# 4digitSSD-MAX7219CNG.net
KiCad netlist of a schematic drawn in EAGLE
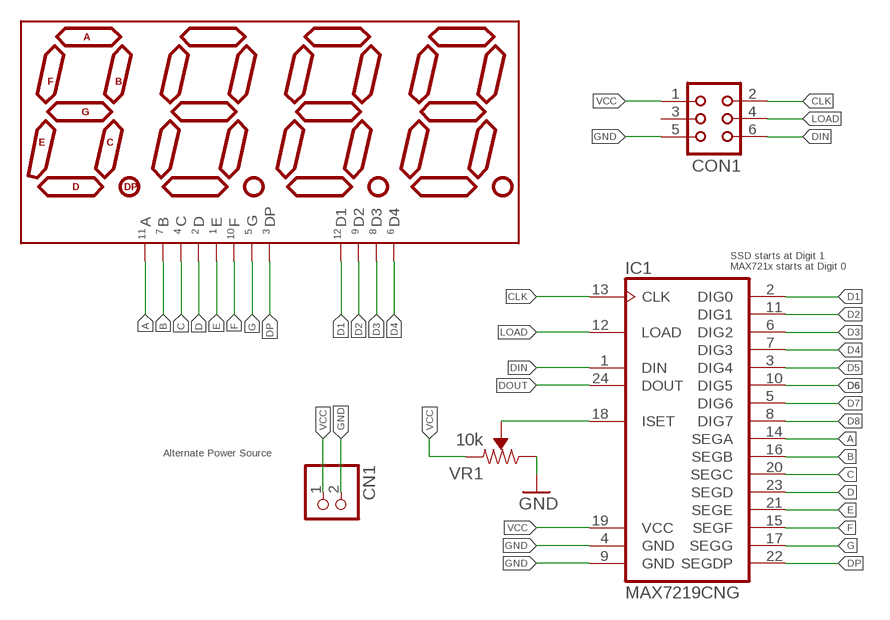
[diagram p0: schematic, sheet 1]

(export (version "E")
  (design (tool "Eeschema 10.0.6"))
  (components
    (comp (ref "CN1")
      (value "JST_2PIN-THM")
      (footprint "eagle-import:JST-PH-2-THM")
      (libsource (lib "eagle-import") (part "JST_2PIN-THM"))
    )
    (comp (ref "CON1")
      (value "CON06")
      (footprint "eagle-import:CON06")
      (libsource (lib "eagle-import") (part "CON06"))
    )
    (comp (ref "IC1")
      (value "MAX7219CNG")
      (footprint "eagle-import:DIL24-3")
      (fields (field (name "MF") "MAXIM"))
      (libsource (lib "eagle-import") (part "MAX7219CNG"))
    )
    (comp (ref "U$1")
      (value "7-SEGMENT-4DIGIT-COUNTERPTH")
      (footprint "eagle-import:7-SEGMENT-4DIGIT-COUNTER")
      (libsource (lib "eagle-import") (part "7-SEGMENT-4DIGIT-COUNTERPTH"))
    )
    (comp (ref "VR1")
      (value "10k")
      (footprint "eagle-import:TRIMPOT-PTH-3386U")
      (libsource (lib "eagle-import") (part "TRIMPOT-PTH-10MM-KNOB-1/2W-10%"))
    )
  )
  (nets
    (net (code "1") (name "A") (class "Default")
      (node (ref "IC1") (pin "14") (pinfunction "SEGA_14") (pintype "output"))
      (node (ref "U$1") (pin "11") (pinfunction "A_11") (pintype "bidirectional"))
    )
    (net (code "2") (name "B") (class "Default")
      (node (ref "IC1") (pin "16") (pinfunction "SEGB_16") (pintype "output"))
      (node (ref "U$1") (pin "7") (pinfunction "B_7") (pintype "bidirectional"))
    )
    (net (code "3") (name "C") (class "Default")
      (node (ref "IC1") (pin "20") (pinfunction "SEGC_20") (pintype "output"))
      (node (ref "U$1") (pin "4") (pinfunction "C_4") (pintype "bidirectional"))
    )
    (net (code "4") (name "CLK") (class "Default")
      (node (ref "CON1") (pin "2") (pinfunction "2_2") (pintype "passive"))
      (node (ref "IC1") (pin "13") (pinfunction "CLK_13") (pintype "input"))
    )
    (net (code "5") (name "D") (class "Default")
      (node (ref "IC1") (pin "23") (pinfunction "SEGD_23") (pintype "output"))
      (node (ref "U$1") (pin "2") (pinfunction "D_2") (pintype "bidirectional"))
    )
    (net (code "6") (name "D1") (class "Default")
      (node (ref "IC1") (pin "2") (pinfunction "DIG0_2") (pintype "output"))
      (node (ref "U$1") (pin "12") (pinfunction "D1_12") (pintype "bidirectional"))
    )
    (net (code "7") (name "D2") (class "Default")
      (node (ref "IC1") (pin "11") (pinfunction "DIG1_11") (pintype "output"))
      (node (ref "U$1") (pin "9") (pinfunction "D2_9") (pintype "bidirectional"))
    )
    (net (code "8") (name "D3") (class "Default")
      (node (ref "IC1") (pin "6") (pinfunction "DIG2_6") (pintype "output"))
      (node (ref "U$1") (pin "8") (pinfunction "D3_8") (pintype "bidirectional"))
    )
    (net (code "9") (name "D4") (class "Default")
      (node (ref "IC1") (pin "7") (pinfunction "DIG3_7") (pintype "output"))
      (node (ref "U$1") (pin "6") (pinfunction "D4_6") (pintype "bidirectional"))
    )
    (net (code "10") (name "D5") (class "Default")
      (node (ref "IC1") (pin "3") (pinfunction "DIG4_3") (pintype "output"))
    )
    (net (code "11") (name "D6") (class "Default")
      (node (ref "IC1") (pin "10") (pinfunction "DIG5_10") (pintype "output"))
    )
    (net (code "12") (name "D7") (class "Default")
      (node (ref "IC1") (pin "5") (pinfunction "DIG6_5") (pintype "output"))
    )
    (net (code "13") (name "D8") (class "Default")
      (node (ref "IC1") (pin "8") (pinfunction "DIG7_8") (pintype "output"))
    )
    (net (code "14") (name "DIN") (class "Default")
      (node (ref "CON1") (pin "6") (pinfunction "6_6") (pintype "passive"))
      (node (ref "IC1") (pin "1") (pinfunction "DIN_1") (pintype "input"))
    )
    (net (code "15") (name "DOUT") (class "Default")
      (node (ref "IC1") (pin "24") (pinfunction "DOUT_24") (pintype "output"))
    )
    (net (code "16") (name "DP") (class "Default")
      (node (ref "IC1") (pin "22") (pinfunction "SEGDP_22") (pintype "output"))
      (node (ref "U$1") (pin "3") (pinfunction "DP_3") (pintype "bidirectional"))
    )
    (net (code "17") (name "E") (class "Default")
      (node (ref "IC1") (pin "21") (pinfunction "SEGE_21") (pintype "output"))
      (node (ref "U$1") (pin "1") (pinfunction "E_1") (pintype "bidirectional"))
    )
    (net (code "18") (name "F") (class "Default")
      (node (ref "IC1") (pin "15") (pinfunction "SEGF_15") (pintype "output"))
      (node (ref "U$1") (pin "10") (pinfunction "F_10") (pintype "bidirectional"))
    )
    (net (code "19") (name "G") (class "Default")
      (node (ref "IC1") (pin "17") (pinfunction "SEGG_17") (pintype "output"))
      (node (ref "U$1") (pin "5") (pinfunction "G_5") (pintype "bidirectional"))
    )
    (net (code "20") (name "GND") (class "Default")
      (node (ref "CN1") (pin "2") (pinfunction "1_2") (pintype "passive"))
      (node (ref "CON1") (pin "5") (pinfunction "5_5") (pintype "passive"))
      (node (ref "IC1") (pin "4") (pinfunction "GND_4") (pintype "power_in"))
      (node (ref "IC1") (pin "9") (pinfunction "GND_9") (pintype "power_in"))
      (node (ref "VR1") (pin "3") (pinfunction "CW_3") (pintype "passive"))
    )
    (net (code "21") (name "LOAD") (class "Default")
      (node (ref "CON1") (pin "4") (pinfunction "4_4") (pintype "passive"))
      (node (ref "IC1") (pin "12") (pinfunction "LOAD_12") (pintype "input"))
    )
    (net (code "22") (name "Net-(IC1-ISET)") (class "Default")
      (node (ref "IC1") (pin "18") (pinfunction "ISET_18") (pintype "input"))
      (node (ref "VR1") (pin "2") (pinfunction "WIPER_2") (pintype "passive"))
    )
    (net (code "23") (name "VCC") (class "Default")
      (node (ref "CN1") (pin "1") (pinfunction "2_1") (pintype "passive"))
      (node (ref "CON1") (pin "1") (pinfunction "1_1") (pintype "passive"))
      (node (ref "IC1") (pin "19") (pinfunction "VCC_19") (pintype "power_in"))
      (node (ref "VR1") (pin "1") (pinfunction "CCW_1") (pintype "passive"))
    )
    (net (code "24") (name "unconnected-(CON1-Pad3)") (class "Default")
      (node (ref "CON1") (pin "3") (pinfunction "3_3") (pintype "passive"))
    )
  )
)
